# Carte__lectronique_contoleur_midi.net
KiCad netlist of a schematic drawn in EAGLE
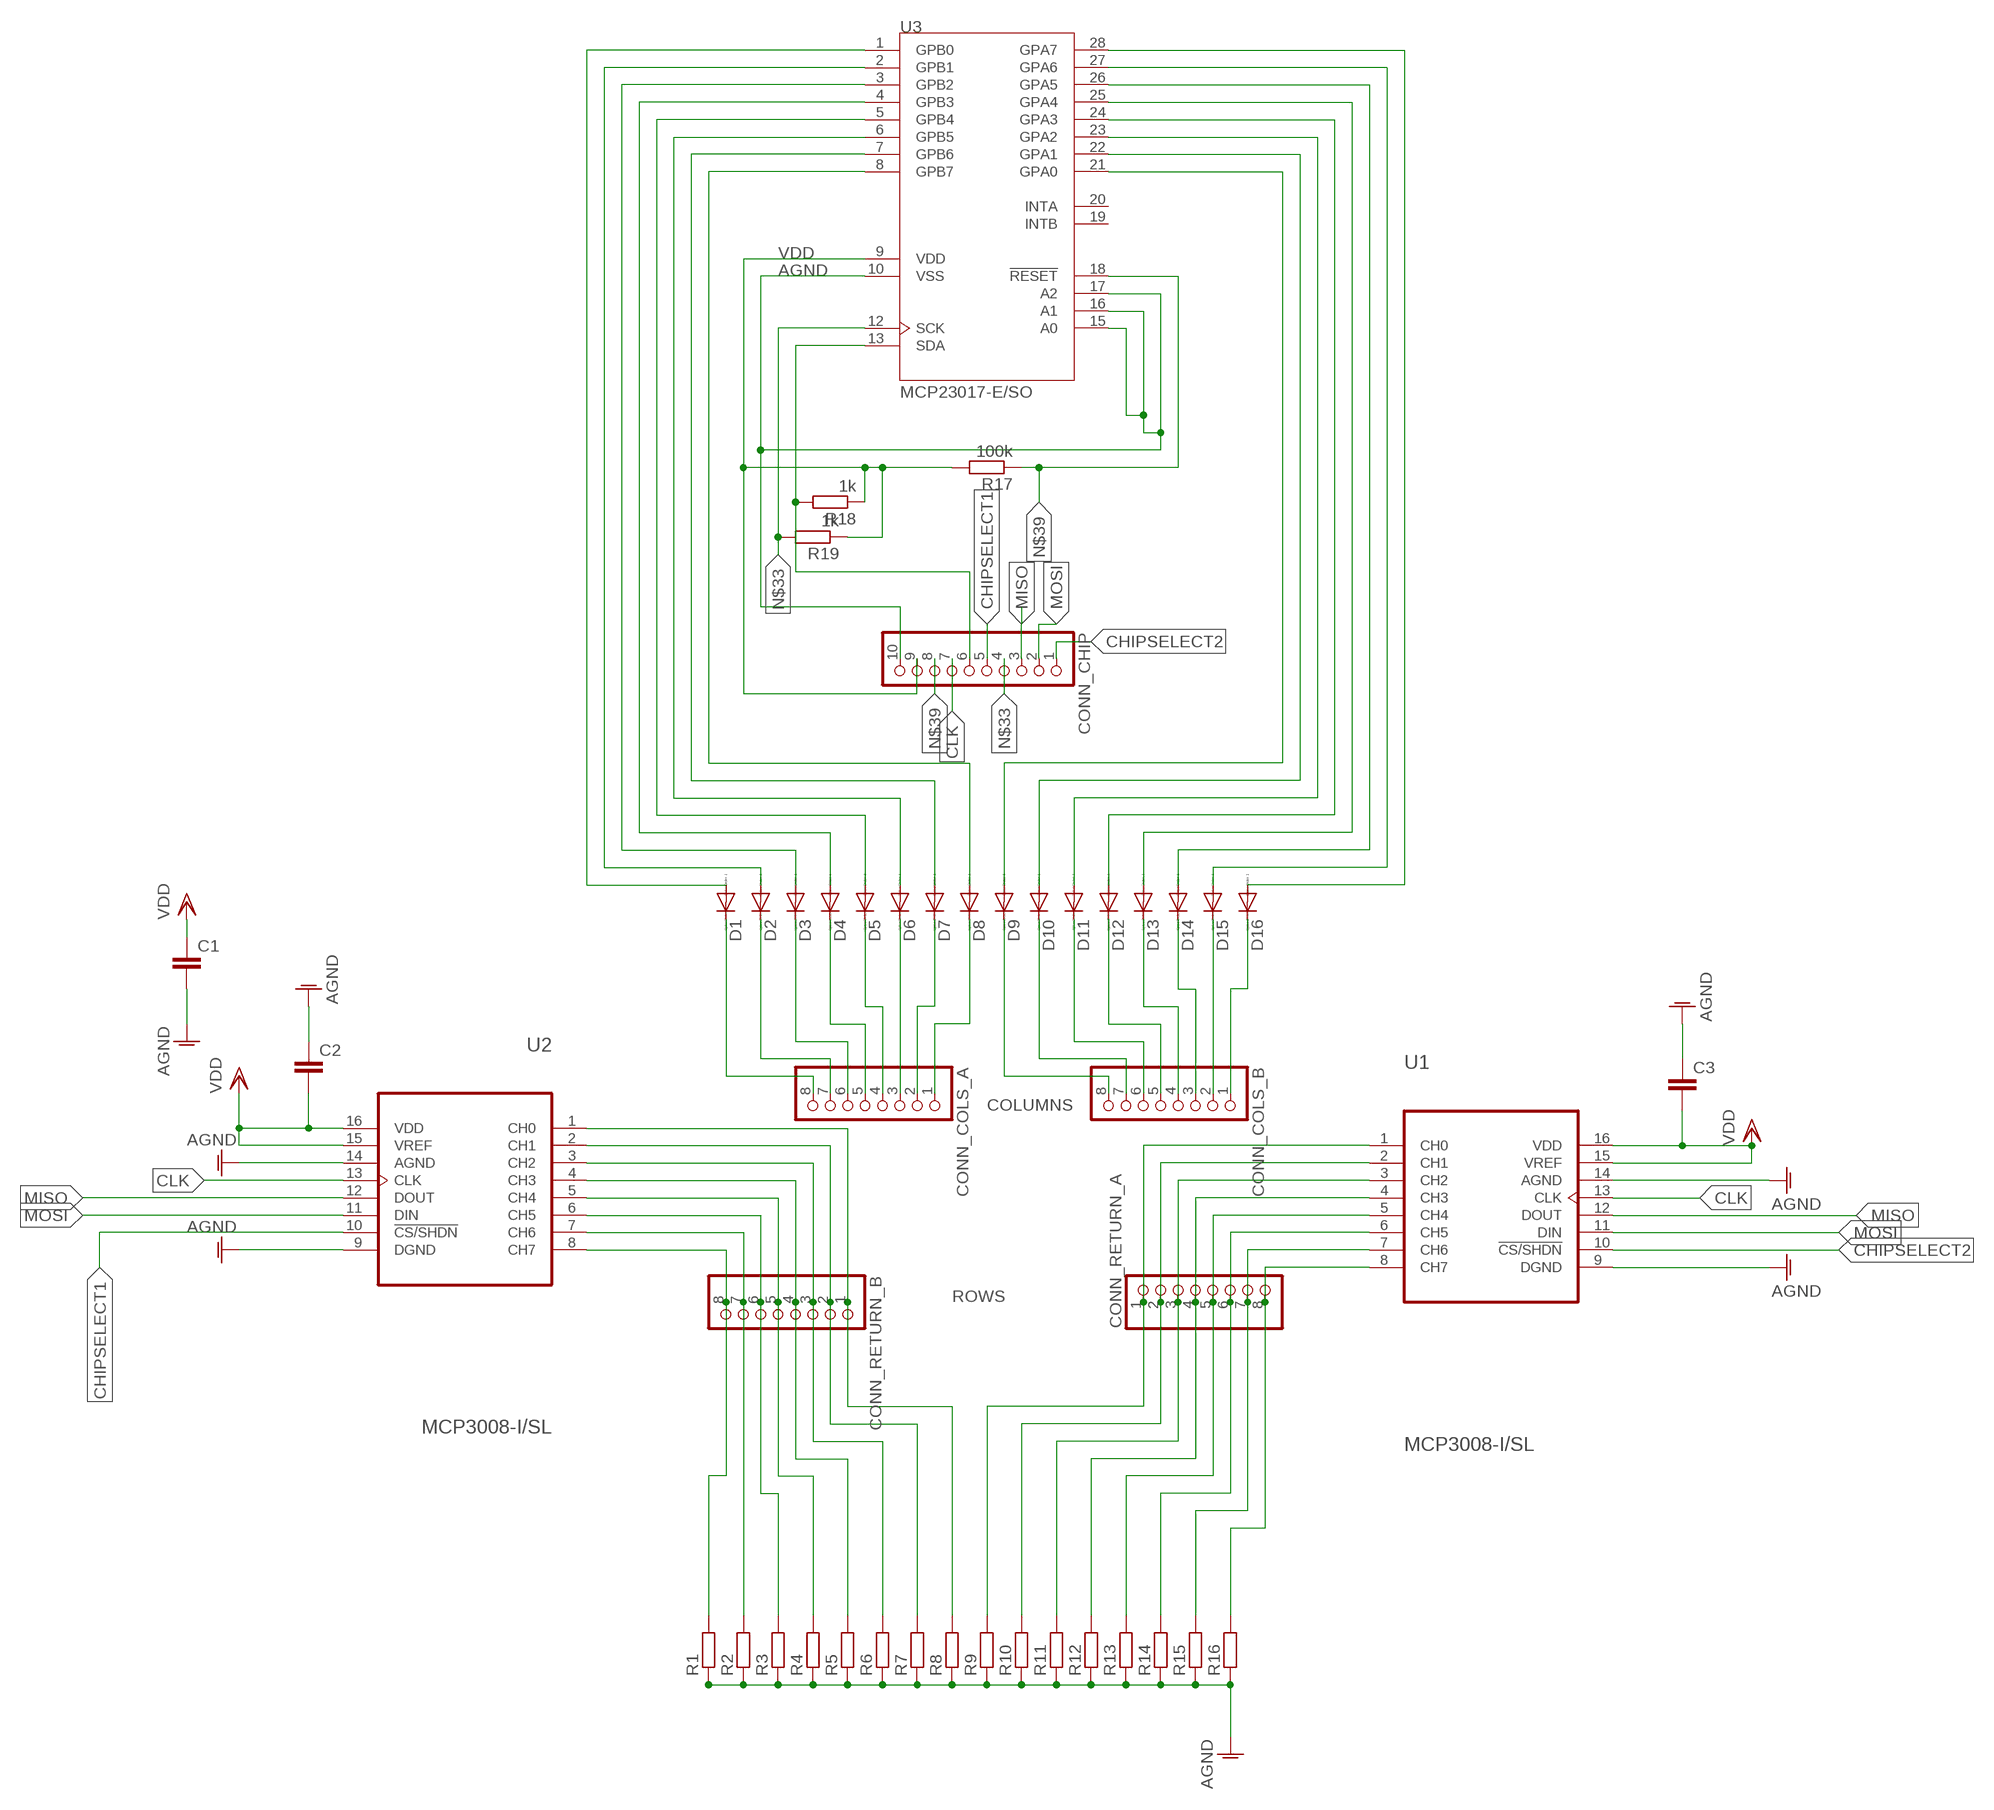
[diagram p0: schematic, sheet 1]

(export (version "E")
  (design (tool "Eeschema 10.0.6"))
  (components
    (comp (ref "C1")
      (value "C-EUC1206K")
      (footprint "eagle-import:C1206K")
      (libsource (lib "eagle-import") (part "C-EUC1206K"))
    )
    (comp (ref "C2")
      (value "C-EUC1206K")
      (footprint "eagle-import:C1206K")
      (libsource (lib "eagle-import") (part "C-EUC1206K"))
    )
    (comp (ref "C3")
      (value "C-EUC1206K")
      (footprint "eagle-import:C1206K")
      (libsource (lib "eagle-import") (part "C-EUC1206K"))
    )
    (comp (ref "CONN_CHIP")
      (value "PINHD-1X10/90")
      (footprint "eagle-import:1X10_90")
      (libsource (lib "eagle-import") (part "PINHD-1X10/90"))
    )
    (comp (ref "CONN_COLS_A")
      (value "PINHD-1X8/90")
      (footprint "eagle-import:1X08_90")
      (libsource (lib "eagle-import") (part "PINHD-1X8/90"))
    )
    (comp (ref "CONN_COLS_B")
      (value "PINHD-1X8/90")
      (footprint "eagle-import:1X08_90")
      (libsource (lib "eagle-import") (part "PINHD-1X8/90"))
    )
    (comp (ref "CONN_RETURN_A")
      (value "PINHD-1X8/90")
      (footprint "eagle-import:1X08_90")
      (libsource (lib "eagle-import") (part "PINHD-1X8/90"))
    )
    (comp (ref "CONN_RETURN_B")
      (value "PINHD-1X8/90")
      (footprint "eagle-import:1X08_90")
      (libsource (lib "eagle-import") (part "PINHD-1X8/90"))
    )
    (comp (ref "D1")
      (value "DIODE-SOD323-W")
      (footprint "eagle-import:SOD323-W")
      (libsource (lib "eagle-import") (part "DIODE-SOD323-W"))
    )
    (comp (ref "D2")
      (value "DIODE-SOD323-W")
      (footprint "eagle-import:SOD323-W")
      (libsource (lib "eagle-import") (part "DIODE-SOD323-W"))
    )
    (comp (ref "D3")
      (value "DIODE-SOD323-W")
      (footprint "eagle-import:SOD323-W")
      (libsource (lib "eagle-import") (part "DIODE-SOD323-W"))
    )
    (comp (ref "D4")
      (value "DIODE-SOD323-W")
      (footprint "eagle-import:SOD323-W")
      (libsource (lib "eagle-import") (part "DIODE-SOD323-W"))
    )
    (comp (ref "D5")
      (value "DIODE-SOD323-W")
      (footprint "eagle-import:SOD323-W")
      (libsource (lib "eagle-import") (part "DIODE-SOD323-W"))
    )
    (comp (ref "D6")
      (value "DIODE-SOD323-W")
      (footprint "eagle-import:SOD323-W")
      (libsource (lib "eagle-import") (part "DIODE-SOD323-W"))
    )
    (comp (ref "D7")
      (value "DIODE-SOD323-W")
      (footprint "eagle-import:SOD323-W")
      (libsource (lib "eagle-import") (part "DIODE-SOD323-W"))
    )
    (comp (ref "D8")
      (value "DIODE-SOD323-W")
      (footprint "eagle-import:SOD323-W")
      (libsource (lib "eagle-import") (part "DIODE-SOD323-W"))
    )
    (comp (ref "D9")
      (value "DIODE-SOD323-W")
      (footprint "eagle-import:SOD323-W")
      (libsource (lib "eagle-import") (part "DIODE-SOD323-W"))
    )
    (comp (ref "D10")
      (value "DIODE-SOD323-W")
      (footprint "eagle-import:SOD323-W")
      (libsource (lib "eagle-import") (part "DIODE-SOD323-W"))
    )
    (comp (ref "D11")
      (value "DIODE-SOD323-W")
      (footprint "eagle-import:SOD323-W")
      (libsource (lib "eagle-import") (part "DIODE-SOD323-W"))
    )
    (comp (ref "D12")
      (value "DIODE-SOD323-W")
      (footprint "eagle-import:SOD323-W")
      (libsource (lib "eagle-import") (part "DIODE-SOD323-W"))
    )
    (comp (ref "D13")
      (value "DIODE-SOD323-W")
      (footprint "eagle-import:SOD323-W")
      (libsource (lib "eagle-import") (part "DIODE-SOD323-W"))
    )
    (comp (ref "D14")
      (value "DIODE-SOD323-W")
      (footprint "eagle-import:SOD323-W")
      (libsource (lib "eagle-import") (part "DIODE-SOD323-W"))
    )
    (comp (ref "D15")
      (value "DIODE-SOD323-W")
      (footprint "eagle-import:SOD323-W")
      (libsource (lib "eagle-import") (part "DIODE-SOD323-W"))
    )
    (comp (ref "D16")
      (value "DIODE-SOD323-W")
      (footprint "eagle-import:SOD323-W")
      (libsource (lib "eagle-import") (part "DIODE-SOD323-W"))
    )
    (comp (ref "R1")
      (value "R-EU_M1206")
      (footprint "eagle-import:M1206")
      (libsource (lib "eagle-import") (part "R-EU_M1206"))
    )
    (comp (ref "R2")
      (value "R-EU_M1206")
      (footprint "eagle-import:M1206")
      (libsource (lib "eagle-import") (part "R-EU_M1206"))
    )
    (comp (ref "R3")
      (value "R-EU_M1206")
      (footprint "eagle-import:M1206")
      (libsource (lib "eagle-import") (part "R-EU_M1206"))
    )
    (comp (ref "R4")
      (value "R-EU_M1206")
      (footprint "eagle-import:M1206")
      (libsource (lib "eagle-import") (part "R-EU_M1206"))
    )
    (comp (ref "R5")
      (value "R-EU_M1206")
      (footprint "eagle-import:M1206")
      (libsource (lib "eagle-import") (part "R-EU_M1206"))
    )
    (comp (ref "R6")
      (value "R-EU_M1206")
      (footprint "eagle-import:M1206")
      (libsource (lib "eagle-import") (part "R-EU_M1206"))
    )
    (comp (ref "R7")
      (value "R-EU_M1206")
      (footprint "eagle-import:M1206")
      (libsource (lib "eagle-import") (part "R-EU_M1206"))
    )
    (comp (ref "R8")
      (value "R-EU_M1206")
      (footprint "eagle-import:M1206")
      (libsource (lib "eagle-import") (part "R-EU_M1206"))
    )
    (comp (ref "R9")
      (value "R-EU_M1206")
      (footprint "eagle-import:M1206")
      (libsource (lib "eagle-import") (part "R-EU_M1206"))
    )
    (comp (ref "R10")
      (value "R-EU_M1206")
      (footprint "eagle-import:M1206")
      (libsource (lib "eagle-import") (part "R-EU_M1206"))
    )
    (comp (ref "R11")
      (value "R-EU_M1206")
      (footprint "eagle-import:M1206")
      (libsource (lib "eagle-import") (part "R-EU_M1206"))
    )
    (comp (ref "R12")
      (value "R-EU_M1206")
      (footprint "eagle-import:M1206")
      (libsource (lib "eagle-import") (part "R-EU_M1206"))
    )
    (comp (ref "R13")
      (value "R-EU_M1206")
      (footprint "eagle-import:M1206")
      (libsource (lib "eagle-import") (part "R-EU_M1206"))
    )
    (comp (ref "R14")
      (value "R-EU_M1206")
      (footprint "eagle-import:M1206")
      (libsource (lib "eagle-import") (part "R-EU_M1206"))
    )
    (comp (ref "R15")
      (value "R-EU_M1206")
      (footprint "eagle-import:M1206")
      (libsource (lib "eagle-import") (part "R-EU_M1206"))
    )
    (comp (ref "R16")
      (value "R-EU_M1206")
      (footprint "eagle-import:M1206")
      (libsource (lib "eagle-import") (part "R-EU_M1206"))
    )
    (comp (ref "R17")
      (value "100k")
      (footprint "eagle-import:M1206")
      (libsource (lib "eagle-import") (part "R-EU_M1206"))
    )
    (comp (ref "R18")
      (value "1k")
      (footprint "eagle-import:M1206")
      (libsource (lib "eagle-import") (part "R-EU_M1206"))
    )
    (comp (ref "R19")
      (value "1k")
      (footprint "eagle-import:M1206")
      (libsource (lib "eagle-import") (part "R-EU_M1206"))
    )
    (comp (ref "U1")
      (value "MCP3008-I/SL")
      (footprint "eagle-import:SOIC127P600X175-16N")
      (fields (field (name "MF") "Microchip Technology"))
      (libsource (lib "eagle-import") (part "MCP3008-I/SL"))
    )
    (comp (ref "U2")
      (value "MCP3008-I/SL")
      (footprint "eagle-import:SOIC127P600X175-16N")
      (fields (field (name "MF") "Microchip Technology"))
      (libsource (lib "eagle-import") (part "MCP3008-I/SL"))
    )
    (comp (ref "U3")
      (value "MCP23017-E/SO")
      (footprint "eagle-import:SOIC127P1030X265-28N")
      (fields (field (name "MF") "Microchip Technology"))
      (libsource (lib "eagle-import") (part "MCP23017-E/SO"))
    )
  )
  (nets
    (net (code "1") (name "AGND") (class "Default")
      (node (ref "C1") (pin "2") (pinfunction "2_2") (pintype "passive"))
      (node (ref "C2") (pin "1") (pinfunction "1_1") (pintype "passive"))
      (node (ref "C3") (pin "1") (pinfunction "1_1") (pintype "passive"))
      (node (ref "CONN_CHIP") (pin "10") (pinfunction "10_10") (pintype "passive"))
      (node (ref "R1") (pin "1") (pinfunction "1_1") (pintype "passive"))
      (node (ref "R10") (pin "1") (pinfunction "1_1") (pintype "passive"))
      (node (ref "R11") (pin "1") (pinfunction "1_1") (pintype "passive"))
      (node (ref "R12") (pin "1") (pinfunction "1_1") (pintype "passive"))
      (node (ref "R13") (pin "1") (pinfunction "1_1") (pintype "passive"))
      (node (ref "R14") (pin "1") (pinfunction "1_1") (pintype "passive"))
      (node (ref "R15") (pin "1") (pinfunction "1_1") (pintype "passive"))
      (node (ref "R16") (pin "1") (pinfunction "1_1") (pintype "passive"))
      (node (ref "R2") (pin "1") (pinfunction "1_1") (pintype "passive"))
      (node (ref "R3") (pin "1") (pinfunction "1_1") (pintype "passive"))
      (node (ref "R4") (pin "1") (pinfunction "1_1") (pintype "passive"))
      (node (ref "R5") (pin "1") (pinfunction "1_1") (pintype "passive"))
      (node (ref "R6") (pin "1") (pinfunction "1_1") (pintype "passive"))
      (node (ref "R7") (pin "1") (pinfunction "1_1") (pintype "passive"))
      (node (ref "R8") (pin "1") (pinfunction "1_1") (pintype "passive"))
      (node (ref "R9") (pin "1") (pinfunction "1_1") (pintype "passive"))
      (node (ref "U1") (pin "14") (pinfunction "AGND_14") (pintype "power_in"))
      (node (ref "U1") (pin "9") (pinfunction "DGND_9") (pintype "power_in"))
      (node (ref "U2") (pin "14") (pinfunction "AGND_14") (pintype "power_in"))
      (node (ref "U2") (pin "9") (pinfunction "DGND_9") (pintype "power_in"))
      (node (ref "U3") (pin "10") (pinfunction "VSS_10") (pintype "power_in"))
      (node (ref "U3") (pin "15") (pinfunction "A0_15") (pintype "input"))
      (node (ref "U3") (pin "16") (pinfunction "A1_16") (pintype "input"))
      (node (ref "U3") (pin "17") (pinfunction "A2_17") (pintype "input"))
    )
    (net (code "2") (name "CHIPSELECT1") (class "Default")
      (node (ref "CONN_CHIP") (pin "5") (pinfunction "5_5") (pintype "passive"))
      (node (ref "U2") (pin "10") (pinfunction "~{CS/SHDN}_10") (pintype "input"))
    )
    (net (code "3") (name "CHIPSELECT2") (class "Default")
      (node (ref "CONN_CHIP") (pin "1") (pinfunction "1_1") (pintype "passive"))
      (node (ref "U1") (pin "10") (pinfunction "~{CS/SHDN}_10") (pintype "input"))
    )
    (net (code "4") (name "CLK") (class "Default")
      (node (ref "CONN_CHIP") (pin "7") (pinfunction "7_7") (pintype "passive"))
      (node (ref "U1") (pin "13") (pinfunction "CLK_13") (pintype "input"))
      (node (ref "U2") (pin "13") (pinfunction "CLK_13") (pintype "input"))
    )
    (net (code "5") (name "MISO") (class "Default")
      (node (ref "CONN_CHIP") (pin "3") (pinfunction "3_3") (pintype "passive"))
      (node (ref "U1") (pin "12") (pinfunction "DOUT_12") (pintype "output"))
      (node (ref "U2") (pin "12") (pinfunction "DOUT_12") (pintype "output"))
    )
    (net (code "6") (name "MOSI") (class "Default")
      (node (ref "CONN_CHIP") (pin "2") (pinfunction "2_2") (pintype "passive"))
      (node (ref "U1") (pin "11") (pinfunction "DIN_11") (pintype "input"))
      (node (ref "U2") (pin "11") (pinfunction "DIN_11") (pintype "input"))
    )
    (net (code "7") (name "N$33") (class "Default")
      (node (ref "CONN_CHIP") (pin "4") (pinfunction "4_4") (pintype "passive"))
      (node (ref "R19") (pin "2") (pinfunction "2_2") (pintype "passive"))
      (node (ref "U3") (pin "12") (pinfunction "SCK_12") (pintype "input"))
    )
    (net (code "8") (name "N$39") (class "Default")
      (node (ref "CONN_CHIP") (pin "8") (pinfunction "8_8") (pintype "passive"))
      (node (ref "R17") (pin "1") (pinfunction "1_1") (pintype "passive"))
      (node (ref "U3") (pin "18") (pinfunction "~{RESET}_18") (pintype "output"))
    )
    (net (code "9") (name "Net-(CONN_COLS_A-Pad1)") (class "Default")
      (node (ref "CONN_COLS_A") (pin "1") (pinfunction "1_1") (pintype "passive"))
      (node (ref "D8") (pin "C") (pinfunction "C_C") (pintype "passive"))
    )
    (net (code "10") (name "Net-(CONN_COLS_A-Pad2)") (class "Default")
      (node (ref "CONN_COLS_A") (pin "2") (pinfunction "2_2") (pintype "passive"))
      (node (ref "D7") (pin "C") (pinfunction "C_C") (pintype "passive"))
    )
    (net (code "11") (name "Net-(CONN_COLS_A-Pad3)") (class "Default")
      (node (ref "CONN_COLS_A") (pin "3") (pinfunction "3_3") (pintype "passive"))
      (node (ref "D6") (pin "C") (pinfunction "C_C") (pintype "passive"))
    )
    (net (code "12") (name "Net-(CONN_COLS_A-Pad4)") (class "Default")
      (node (ref "CONN_COLS_A") (pin "4") (pinfunction "4_4") (pintype "passive"))
      (node (ref "D5") (pin "C") (pinfunction "C_C") (pintype "passive"))
    )
    (net (code "13") (name "Net-(CONN_COLS_A-Pad5)") (class "Default")
      (node (ref "CONN_COLS_A") (pin "5") (pinfunction "5_5") (pintype "passive"))
      (node (ref "D4") (pin "C") (pinfunction "C_C") (pintype "passive"))
    )
    (net (code "14") (name "Net-(CONN_COLS_A-Pad6)") (class "Default")
      (node (ref "CONN_COLS_A") (pin "6") (pinfunction "6_6") (pintype "passive"))
      (node (ref "D3") (pin "C") (pinfunction "C_C") (pintype "passive"))
    )
    (net (code "15") (name "Net-(CONN_COLS_A-Pad7)") (class "Default")
      (node (ref "CONN_COLS_A") (pin "7") (pinfunction "7_7") (pintype "passive"))
      (node (ref "D2") (pin "C") (pinfunction "C_C") (pintype "passive"))
    )
    (net (code "16") (name "Net-(CONN_COLS_A-Pad8)") (class "Default")
      (node (ref "CONN_COLS_A") (pin "8") (pinfunction "8_8") (pintype "passive"))
      (node (ref "D1") (pin "C") (pinfunction "C_C") (pintype "passive"))
    )
    (net (code "17") (name "Net-(CONN_COLS_B-Pad1)") (class "Default")
      (node (ref "CONN_COLS_B") (pin "1") (pinfunction "1_1") (pintype "passive"))
      (node (ref "D16") (pin "C") (pinfunction "C_C") (pintype "passive"))
    )
    (net (code "18") (name "Net-(CONN_COLS_B-Pad2)") (class "Default")
      (node (ref "CONN_COLS_B") (pin "2") (pinfunction "2_2") (pintype "passive"))
      (node (ref "D15") (pin "C") (pinfunction "C_C") (pintype "passive"))
    )
    (net (code "19") (name "Net-(CONN_COLS_B-Pad3)") (class "Default")
      (node (ref "CONN_COLS_B") (pin "3") (pinfunction "3_3") (pintype "passive"))
      (node (ref "D14") (pin "C") (pinfunction "C_C") (pintype "passive"))
    )
    (net (code "20") (name "Net-(CONN_COLS_B-Pad4)") (class "Default")
      (node (ref "CONN_COLS_B") (pin "4") (pinfunction "4_4") (pintype "passive"))
      (node (ref "D13") (pin "C") (pinfunction "C_C") (pintype "passive"))
    )
    (net (code "21") (name "Net-(CONN_COLS_B-Pad5)") (class "Default")
      (node (ref "CONN_COLS_B") (pin "5") (pinfunction "5_5") (pintype "passive"))
      (node (ref "D12") (pin "C") (pinfunction "C_C") (pintype "passive"))
    )
    (net (code "22") (name "Net-(CONN_COLS_B-Pad6)") (class "Default")
      (node (ref "CONN_COLS_B") (pin "6") (pinfunction "6_6") (pintype "passive"))
      (node (ref "D11") (pin "C") (pinfunction "C_C") (pintype "passive"))
    )
    (net (code "23") (name "Net-(CONN_COLS_B-Pad7)") (class "Default")
      (node (ref "CONN_COLS_B") (pin "7") (pinfunction "7_7") (pintype "passive"))
      (node (ref "D10") (pin "C") (pinfunction "C_C") (pintype "passive"))
    )
    (net (code "24") (name "Net-(CONN_COLS_B-Pad8)") (class "Default")
      (node (ref "CONN_COLS_B") (pin "8") (pinfunction "8_8") (pintype "passive"))
      (node (ref "D9") (pin "C") (pinfunction "C_C") (pintype "passive"))
    )
    (net (code "25") (name "Net-(U1-CH0)") (class "Default")
      (node (ref "CONN_RETURN_A") (pin "1") (pinfunction "1_1") (pintype "passive"))
      (node (ref "R9") (pin "2") (pinfunction "2_2") (pintype "passive"))
      (node (ref "U1") (pin "1") (pinfunction "CH0_1") (pintype "input"))
    )
    (net (code "26") (name "Net-(U1-CH1)") (class "Default")
      (node (ref "CONN_RETURN_A") (pin "2") (pinfunction "2_2") (pintype "passive"))
      (node (ref "R10") (pin "2") (pinfunction "2_2") (pintype "passive"))
      (node (ref "U1") (pin "2") (pinfunction "CH1_2") (pintype "input"))
    )
    (net (code "27") (name "Net-(U1-CH2)") (class "Default")
      (node (ref "CONN_RETURN_A") (pin "3") (pinfunction "3_3") (pintype "passive"))
      (node (ref "R11") (pin "2") (pinfunction "2_2") (pintype "passive"))
      (node (ref "U1") (pin "3") (pinfunction "CH2_3") (pintype "input"))
    )
    (net (code "28") (name "Net-(U1-CH3)") (class "Default")
      (node (ref "CONN_RETURN_A") (pin "4") (pinfunction "4_4") (pintype "passive"))
      (node (ref "R12") (pin "2") (pinfunction "2_2") (pintype "passive"))
      (node (ref "U1") (pin "4") (pinfunction "CH3_4") (pintype "input"))
    )
    (net (code "29") (name "Net-(U1-CH4)") (class "Default")
      (node (ref "CONN_RETURN_A") (pin "5") (pinfunction "5_5") (pintype "passive"))
      (node (ref "R13") (pin "2") (pinfunction "2_2") (pintype "passive"))
      (node (ref "U1") (pin "5") (pinfunction "CH4_5") (pintype "input"))
    )
    (net (code "30") (name "Net-(U1-CH5)") (class "Default")
      (node (ref "CONN_RETURN_A") (pin "6") (pinfunction "6_6") (pintype "passive"))
      (node (ref "R14") (pin "2") (pinfunction "2_2") (pintype "passive"))
      (node (ref "U1") (pin "6") (pinfunction "CH5_6") (pintype "input"))
    )
    (net (code "31") (name "Net-(U1-CH6)") (class "Default")
      (node (ref "CONN_RETURN_A") (pin "7") (pinfunction "7_7") (pintype "passive"))
      (node (ref "R15") (pin "2") (pinfunction "2_2") (pintype "passive"))
      (node (ref "U1") (pin "7") (pinfunction "CH6_7") (pintype "input"))
    )
    (net (code "32") (name "Net-(U1-CH7)") (class "Default")
      (node (ref "CONN_RETURN_A") (pin "8") (pinfunction "8_8") (pintype "passive"))
      (node (ref "R16") (pin "2") (pinfunction "2_2") (pintype "passive"))
      (node (ref "U1") (pin "8") (pinfunction "CH7_8") (pintype "input"))
    )
    (net (code "33") (name "Net-(U2-CH0)") (class "Default")
      (node (ref "CONN_RETURN_B") (pin "1") (pinfunction "1_1") (pintype "passive"))
      (node (ref "R8") (pin "2") (pinfunction "2_2") (pintype "passive"))
      (node (ref "U2") (pin "1") (pinfunction "CH0_1") (pintype "input"))
    )
    (net (code "34") (name "Net-(U2-CH1)") (class "Default")
      (node (ref "CONN_RETURN_B") (pin "2") (pinfunction "2_2") (pintype "passive"))
      (node (ref "R7") (pin "2") (pinfunction "2_2") (pintype "passive"))
      (node (ref "U2") (pin "2") (pinfunction "CH1_2") (pintype "input"))
    )
    (net (code "35") (name "Net-(U2-CH2)") (class "Default")
      (node (ref "CONN_RETURN_B") (pin "3") (pinfunction "3_3") (pintype "passive"))
      (node (ref "R6") (pin "2") (pinfunction "2_2") (pintype "passive"))
      (node (ref "U2") (pin "3") (pinfunction "CH2_3") (pintype "input"))
    )
    (net (code "36") (name "Net-(U2-CH3)") (class "Default")
      (node (ref "CONN_RETURN_B") (pin "4") (pinfunction "4_4") (pintype "passive"))
      (node (ref "R5") (pin "2") (pinfunction "2_2") (pintype "passive"))
      (node (ref "U2") (pin "4") (pinfunction "CH3_4") (pintype "input"))
    )
    (net (code "37") (name "Net-(U2-CH4)") (class "Default")
      (node (ref "CONN_RETURN_B") (pin "5") (pinfunction "5_5") (pintype "passive"))
      (node (ref "R4") (pin "2") (pinfunction "2_2") (pintype "passive"))
      (node (ref "U2") (pin "5") (pinfunction "CH4_5") (pintype "input"))
    )
    (net (code "38") (name "Net-(U2-CH5)") (class "Default")
      (node (ref "CONN_RETURN_B") (pin "6") (pinfunction "6_6") (pintype "passive"))
      (node (ref "R3") (pin "2") (pinfunction "2_2") (pintype "passive"))
      (node (ref "U2") (pin "6") (pinfunction "CH5_6") (pintype "input"))
    )
    (net (code "39") (name "Net-(U2-CH6)") (class "Default")
      (node (ref "CONN_RETURN_B") (pin "7") (pinfunction "7_7") (pintype "passive"))
      (node (ref "R2") (pin "2") (pinfunction "2_2") (pintype "passive"))
      (node (ref "U2") (pin "7") (pinfunction "CH6_7") (pintype "input"))
    )
    (net (code "40") (name "Net-(U2-CH7)") (class "Default")
      (node (ref "CONN_RETURN_B") (pin "8") (pinfunction "8_8") (pintype "passive"))
      (node (ref "R1") (pin "2") (pinfunction "2_2") (pintype "passive"))
      (node (ref "U2") (pin "8") (pinfunction "CH7_8") (pintype "input"))
    )
    (net (code "41") (name "Net-(U3-GPA0)") (class "Default")
      (node (ref "D9") (pin "A") (pinfunction "A_A") (pintype "passive"))
      (node (ref "U3") (pin "21") (pinfunction "GPA0_21") (pintype "bidirectional"))
    )
    (net (code "42") (name "Net-(U3-GPA1)") (class "Default")
      (node (ref "D10") (pin "A") (pinfunction "A_A") (pintype "passive"))
      (node (ref "U3") (pin "22") (pinfunction "GPA1_22") (pintype "bidirectional"))
    )
    (net (code "43") (name "Net-(U3-GPA2)") (class "Default")
      (node (ref "D11") (pin "A") (pinfunction "A_A") (pintype "passive"))
      (node (ref "U3") (pin "23") (pinfunction "GPA2_23") (pintype "bidirectional"))
    )
    (net (code "44") (name "Net-(U3-GPA3)") (class "Default")
      (node (ref "D12") (pin "A") (pinfunction "A_A") (pintype "passive"))
      (node (ref "U3") (pin "24") (pinfunction "GPA3_24") (pintype "bidirectional"))
    )
    (net (code "45") (name "Net-(U3-GPA4)") (class "Default")
      (node (ref "D13") (pin "A") (pinfunction "A_A") (pintype "passive"))
      (node (ref "U3") (pin "25") (pinfunction "GPA4_25") (pintype "bidirectional"))
    )
    (net (code "46") (name "Net-(U3-GPA5)") (class "Default")
      (node (ref "D14") (pin "A") (pinfunction "A_A") (pintype "passive"))
      (node (ref "U3") (pin "26") (pinfunction "GPA5_26") (pintype "bidirectional"))
    )
    (net (code "47") (name "Net-(U3-GPA6)") (class "Default")
      (node (ref "D15") (pin "A") (pinfunction "A_A") (pintype "passive"))
      (node (ref "U3") (pin "27") (pinfunction "GPA6_27") (pintype "bidirectional"))
    )
    (net (code "48") (name "Net-(U3-GPA7)") (class "Default")
      (node (ref "D16") (pin "A") (pinfunction "A_A") (pintype "passive"))
      (node (ref "U3") (pin "28") (pinfunction "GPA7_28") (pintype "bidirectional"))
    )
    (net (code "49") (name "Net-(U3-GPB0)") (class "Default")
      (node (ref "D1") (pin "A") (pinfunction "A_A") (pintype "passive"))
      (node (ref "U3") (pin "1") (pinfunction "GPB0_1") (pintype "bidirectional"))
    )
    (net (code "50") (name "Net-(U3-GPB1)") (class "Default")
      (node (ref "D2") (pin "A") (pinfunction "A_A") (pintype "passive"))
      (node (ref "U3") (pin "2") (pinfunction "GPB1_2") (pintype "bidirectional"))
    )
    (net (code "51") (name "Net-(U3-GPB2)") (class "Default")
      (node (ref "D3") (pin "A") (pinfunction "A_A") (pintype "passive"))
      (node (ref "U3") (pin "3") (pinfunction "GPB2_3") (pintype "bidirectional"))
    )
    (net (code "52") (name "Net-(U3-GPB3)") (class "Default")
      (node (ref "D4") (pin "A") (pinfunction "A_A") (pintype "passive"))
      (node (ref "U3") (pin "4") (pinfunction "GPB3_4") (pintype "bidirectional"))
    )
    (net (code "53") (name "Net-(U3-GPB4)") (class "Default")
      (node (ref "D5") (pin "A") (pinfunction "A_A") (pintype "passive"))
      (node (ref "U3") (pin "5") (pinfunction "GPB4_5") (pintype "bidirectional"))
    )
    (net (code "54") (name "Net-(U3-GPB5)") (class "Default")
      (node (ref "D6") (pin "A") (pinfunction "A_A") (pintype "passive"))
      (node (ref "U3") (pin "6") (pinfunction "GPB5_6") (pintype "bidirectional"))
    )
    (net (code "55") (name "Net-(U3-GPB6)") (class "Default")
      (node (ref "D7") (pin "A") (pinfunction "A_A") (pintype "passive"))
      (node (ref "U3") (pin "7") (pinfunction "GPB6_7") (pintype "bidirectional"))
    )
    (net (code "56") (name "Net-(U3-GPB7)") (class "Default")
      (node (ref "D8") (pin "A") (pinfunction "A_A") (pintype "passive"))
      (node (ref "U3") (pin "8") (pinfunction "GPB7_8") (pintype "bidirectional"))
    )
    (net (code "57") (name "Net-(U3-SDA)") (class "Default")
      (node (ref "CONN_CHIP") (pin "6") (pinfunction "6_6") (pintype "passive"))
      (node (ref "R18") (pin "2") (pinfunction "2_2") (pintype "passive"))
      (node (ref "U3") (pin "13") (pinfunction "SDA_13") (pintype "bidirectional"))
    )
    (net (code "58") (name "VDD") (class "Default")
      (node (ref "C1") (pin "1") (pinfunction "1_1") (pintype "passive"))
      (node (ref "C2") (pin "2") (pinfunction "2_2") (pintype "passive"))
      (node (ref "C3") (pin "2") (pinfunction "2_2") (pintype "passive"))
      (node (ref "CONN_CHIP") (pin "9") (pinfunction "9_9") (pintype "passive"))
      (node (ref "R17") (pin "2") (pinfunction "2_2") (pintype "passive"))
      (node (ref "R18") (pin "1") (pinfunction "1_1") (pintype "passive"))
      (node (ref "R19") (pin "1") (pinfunction "1_1") (pintype "passive"))
      (node (ref "U1") (pin "15") (pinfunction "VREF_15") (pintype "input"))
      (node (ref "U1") (pin "16") (pinfunction "VDD_16") (pintype "power_in"))
      (node (ref "U2") (pin "15") (pinfunction "VREF_15") (pintype "input"))
      (node (ref "U2") (pin "16") (pinfunction "VDD_16") (pintype "power_in"))
      (node (ref "U3") (pin "9") (pinfunction "VDD_9") (pintype "power_in"))
    )
    (net (code "59") (name "unconnected-(U3-INTA-Pad20)") (class "Default")
      (node (ref "U3") (pin "20") (pinfunction "INTA_20") (pintype "output"))
    )
    (net (code "60") (name "unconnected-(U3-INTB-Pad19)") (class "Default")
      (node (ref "U3") (pin "19") (pinfunction "INTB_19") (pintype "output"))
    )
  )
)
